# Micro.net
KiCad netlist of a schematic drawn in Altium Designer
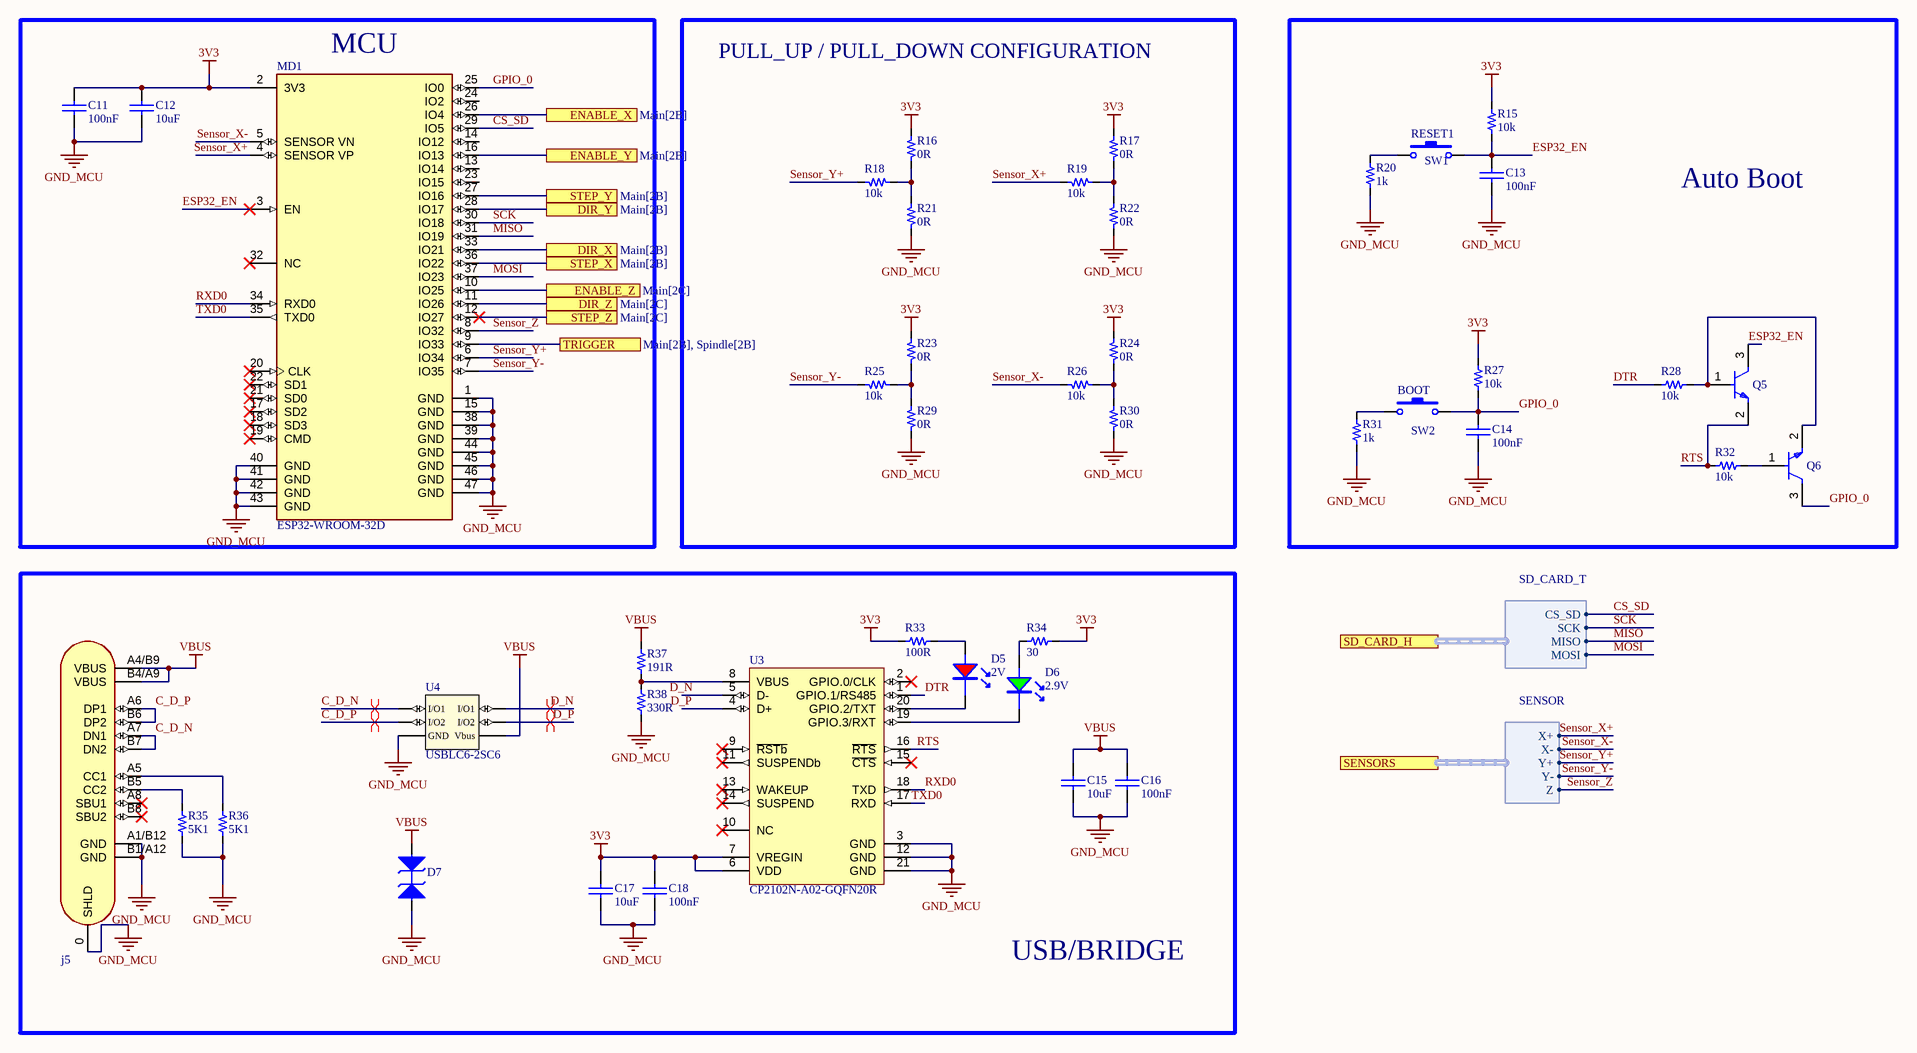
[diagram p0: Micro.SchDoc]

(export (version "E")
  (design (tool "Eeschema 10.0.6"))
  (components
    (comp (ref "C11")
      (value "100nF")
      (footprint "0603_cap")
      (description "50V 100nF X7R ±10% 0603 Ceramic Capacitors RoHS")
      (fields
        (field (name "MANUFACTURER") "FOJAN")
        (field (name "MANUFACTURER PART NUMBER") "FCC0603B104K500CT")
      )
      (libsource (lib "CNCLib") (part "Cap_100nF_0603_50V"))
    )
    (comp (ref "C12")
      (value "10uF")
      (footprint "0603_cap")
      (description "10V 10uF X5R ±10% 0603 Multilayer Ceramic Capacitors MLCC - SMD/SMT ROHS")
      (fields
        (field (name "MANUFACTURER") "CCTC")
        (field (name "MANUFACTURER PART NUMBER") "TCC0603X5R106K100CT")
      )
      (libsource (lib "CNCLib") (part "Cap_10uF_0603_10V"))
    )
    (comp (ref "C13")
      (value "100nF")
      (footprint "0603_cap")
      (description "50V 100nF X7R ±10% 0603 Ceramic Capacitors RoHS")
      (fields
        (field (name "MANUFACTURER") "FOJAN")
        (field (name "MANUFACTURER PART NUMBER") "FCC0603B104K500CT")
      )
      (libsource (lib "CNCLib") (part "Cap_100nF_0603_50V"))
    )
    (comp (ref "C14")
      (value "100nF")
      (footprint "0603_cap")
      (description "50V 100nF X7R ±10% 0603 Ceramic Capacitors RoHS")
      (fields
        (field (name "MANUFACTURER") "FOJAN")
        (field (name "MANUFACTURER PART NUMBER") "FCC0603B104K500CT")
      )
      (libsource (lib "CNCLib") (part "Cap_100nF_0603_50V"))
    )
    (comp (ref "C15")
      (value "10uF")
      (footprint "0603_cap")
      (description "10V 10uF X5R ±10% 0603 Multilayer Ceramic Capacitors MLCC - SMD/SMT ROHS")
      (fields
        (field (name "MANUFACTURER") "CCTC")
        (field (name "MANUFACTURER PART NUMBER") "TCC0603X5R106K100CT")
      )
      (libsource (lib "CNCLib") (part "Cap_10uF_0603_10V"))
    )
    (comp (ref "C16")
      (value "100nF")
      (footprint "0603_cap")
      (description "50V 100nF X7R ±10% 0603 Ceramic Capacitors RoHS")
      (fields
        (field (name "MANUFACTURER") "FOJAN")
        (field (name "MANUFACTURER PART NUMBER") "FCC0603B104K500CT")
      )
      (libsource (lib "CNCLib") (part "Cap_100nF_0603_50V"))
    )
    (comp (ref "C17")
      (value "10uF")
      (footprint "0603_cap")
      (description "10V 10uF X5R ±10% 0603 Multilayer Ceramic Capacitors MLCC - SMD/SMT ROHS")
      (fields
        (field (name "MANUFACTURER") "CCTC")
        (field (name "MANUFACTURER PART NUMBER") "TCC0603X5R106K100CT")
      )
      (libsource (lib "CNCLib") (part "Cap_10uF_0603_10V"))
    )
    (comp (ref "C18")
      (value "100nF")
      (footprint "0603_cap")
      (description "50V 100nF X7R ±10% 0603 Ceramic Capacitors RoHS")
      (fields
        (field (name "MANUFACTURER") "FOJAN")
        (field (name "MANUFACTURER PART NUMBER") "FCC0603B104K500CT")
      )
      (libsource (lib "CNCLib") (part "Cap_100nF_0603_50V"))
    )
    (comp (ref "D5")
      (value "2V")
      (footprint "0805_LED")
      (description "LED RED CLEAR 0805 SMD")
      (fields
        (field (name "MANUFACTURER") "XINGLIGHT")
        (field (name "MANUFACTURER PART NUMBER") "XL-2012SURC")
      )
      (libsource (lib "CNCLib") (part "LED_0805_RED"))
    )
    (comp (ref "D6")
      (value "2.9V")
      (footprint "0805_LED")
      (description "LED GREEN CLEAR 0805 SMD")
      (fields
        (field (name "MANUFACTURER") "XINGLIGHT")
        (field (name "MANUFACTURER PART NUMBER") "XL-2012UGC")
      )
      (libsource (lib "CNCLib") (part "LED_0805_Green"))
    )
    (comp (ref "D7")
      (value "TVS 12V")
      (footprint "SOD_123FL")
      (description "21.7A 200W@10/1000us 9.2V 7V Bidirectional 5V SOD-123FL ESD and Surge Protection (TVS/ESD) ROHS")
      (fields (field (name "MANUFACTURER") "TDSEMIC") (field (name "MANUFACTURER PART NUMBER") "SMF5.0CA"))
      (libsource (lib "CNCLib") (part "TVS_5V_1CH_BID_SOD_123FL"))
    )
    (comp (ref "j5")
      (value "USB C")
      (footprint "CON_USB_C_16P_RA")
      (description "3A USB 3.1 1 Surface Mount 16P Female -40℃~+85℃ Type-C SMD USB Connectors ROHS")
      (fields
        (field (name "MANUFACTURER") "SHOU HAN")
        (field (name "MANUFACTURER PART NUMBER") "TYPE-C-3.1-16PIN")
      )
      (libsource (lib "CNCLib") (part "CON_USB_TYPEC_16P"))
    )
    (comp (ref "MD1")
      (value "ESP32-WROOM-32D")
      (footprint "MOD_ESP32-WROOM-32_EXP")
      (description "WIFI MODULE 32MBITS SPI FLASH")
      (fields
        (field (name "MANUFACTURER") "ESPRESSIF")
        (field (name "MANUFACTURER PART NUMBER") "ESP32-WROOM-32-N4")
      )
      (libsource (lib "CNCLib") (part "CMP-194065-000003-1"))
    )
    (comp (ref "Q5")
      (value "TRANS NPN 40V 200mA SOT-23")
      (footprint "SOT_23_3")
      (description "40V 310mW 200mA NPN SOT-23 Single Bipolar Transistors RoHS")
      (fields (field (name "MANUFACTURER") "DIODES") (field (name "MANUFACTURER PART NUMBER") "MMBT3904-7-F"))
      (libsource (lib "CNCLib") (part "BJT_N_MMBT3904-7-F"))
    )
    (comp (ref "Q6")
      (value "TRANS NPN 40V 200mA SOT-23")
      (footprint "SOT_23_3")
      (description "40V 310mW 200mA NPN SOT-23 Single Bipolar Transistors RoHS")
      (fields (field (name "MANUFACTURER") "DIODES") (field (name "MANUFACTURER PART NUMBER") "MMBT3904-7-F"))
      (libsource (lib "CNCLib") (part "BJT_N_MMBT3904-7-F"))
    )
    (comp (ref "R15")
      (value "10k")
      (footprint "0603_res")
      (description "RES SMD 10k OHM 5% 1/10W 0603")
      (fields (field (name "MANUFACTURER") "FOJAN") (field (name "MANUFACTURER PART NUMBER") "FRC0603J103TS"))
      (libsource (lib "CNCLib") (part "Res_10k_0603_1/10W"))
    )
    (comp (ref "R16")
      (value "0R")
      (footprint "0603_res")
      (description "RES SMD 0R OHM 5% 1/10W 0603")
      (fields
        (field (name "MANUFACTURER") "FOJAN")
        (field (name "MANUFACTURER PART NUMBER") "FRC0603P000 TS")
      )
      (libsource (lib "CNCLib") (part "Res_0R_0603_1/10W"))
    )
    (comp (ref "R17")
      (value "0R")
      (footprint "0603_res")
      (description "RES SMD 0R OHM 5% 1/10W 0603")
      (fields
        (field (name "MANUFACTURER") "FOJAN")
        (field (name "MANUFACTURER PART NUMBER") "FRC0603P000 TS")
      )
      (libsource (lib "CNCLib") (part "Res_0R_0603_1/10W"))
    )
    (comp (ref "R18")
      (value "10k")
      (footprint "0603_res")
      (description "RES SMD 10k OHM 5% 1/10W 0603")
      (fields (field (name "MANUFACTURER") "FOJAN") (field (name "MANUFACTURER PART NUMBER") "FRC0603J103TS"))
      (libsource (lib "CNCLib") (part "Res_10k_0603_1/10W"))
    )
    (comp (ref "R19")
      (value "10k")
      (footprint "0603_res")
      (description "RES SMD 10k OHM 5% 1/10W 0603")
      (fields (field (name "MANUFACTURER") "FOJAN") (field (name "MANUFACTURER PART NUMBER") "FRC0603J103TS"))
      (libsource (lib "CNCLib") (part "Res_10k_0603_1/10W"))
    )
    (comp (ref "R20")
      (value "1k")
      (footprint "0603_res")
      (description "RES SMD 1k OHM 5% 1/10W 0603")
      (fields
        (field (name "MANUFACTURER") "FOJAN")
        (field (name "MANUFACTURER PART NUMBER") "FRC0603J102 TS")
      )
      (libsource (lib "CNCLib") (part "Res_1k_0603_1/10W"))
    )
    (comp (ref "R21")
      (value "0R")
      (footprint "0603_res")
      (description "RES SMD 0R OHM 5% 1/10W 0603")
      (fields
        (field (name "MANUFACTURER") "FOJAN")
        (field (name "MANUFACTURER PART NUMBER") "FRC0603P000 TS")
      )
      (libsource (lib "CNCLib") (part "Res_0R_0603_1/10W"))
    )
    (comp (ref "R22")
      (value "0R")
      (footprint "0603_res")
      (description "RES SMD 0R OHM 5% 1/10W 0603")
      (fields
        (field (name "MANUFACTURER") "FOJAN")
        (field (name "MANUFACTURER PART NUMBER") "FRC0603P000 TS")
      )
      (libsource (lib "CNCLib") (part "Res_0R_0603_1/10W"))
    )
    (comp (ref "R23")
      (value "0R")
      (footprint "0603_res")
      (description "RES SMD 0R OHM 5% 1/10W 0603")
      (fields
        (field (name "MANUFACTURER") "FOJAN")
        (field (name "MANUFACTURER PART NUMBER") "FRC0603P000 TS")
      )
      (libsource (lib "CNCLib") (part "Res_0R_0603_1/10W"))
    )
    (comp (ref "R24")
      (value "0R")
      (footprint "0603_res")
      (description "RES SMD 0R OHM 5% 1/10W 0603")
      (fields
        (field (name "MANUFACTURER") "FOJAN")
        (field (name "MANUFACTURER PART NUMBER") "FRC0603P000 TS")
      )
      (libsource (lib "CNCLib") (part "Res_0R_0603_1/10W"))
    )
    (comp (ref "R25")
      (value "10k")
      (footprint "0603_res")
      (description "RES SMD 10k OHM 5% 1/10W 0603")
      (fields (field (name "MANUFACTURER") "FOJAN") (field (name "MANUFACTURER PART NUMBER") "FRC0603J103TS"))
      (libsource (lib "CNCLib") (part "Res_10k_0603_1/10W"))
    )
    (comp (ref "R26")
      (value "10k")
      (footprint "0603_res")
      (description "RES SMD 10k OHM 5% 1/10W 0603")
      (fields (field (name "MANUFACTURER") "FOJAN") (field (name "MANUFACTURER PART NUMBER") "FRC0603J103TS"))
      (libsource (lib "CNCLib") (part "Res_10k_0603_1/10W"))
    )
    (comp (ref "R27")
      (value "10k")
      (footprint "0603_res")
      (description "RES SMD 10k OHM 5% 1/10W 0603")
      (fields (field (name "MANUFACTURER") "FOJAN") (field (name "MANUFACTURER PART NUMBER") "FRC0603J103TS"))
      (libsource (lib "CNCLib") (part "Res_10k_0603_1/10W"))
    )
    (comp (ref "R28")
      (value "10k")
      (footprint "0603_res")
      (description "RES SMD 10k OHM 5% 1/10W 0603")
      (fields (field (name "MANUFACTURER") "FOJAN") (field (name "MANUFACTURER PART NUMBER") "FRC0603J103TS"))
      (libsource (lib "CNCLib") (part "Res_10k_0603_1/10W"))
    )
    (comp (ref "R29")
      (value "0R")
      (footprint "0603_res")
      (description "RES SMD 0R OHM 5% 1/10W 0603")
      (fields
        (field (name "MANUFACTURER") "FOJAN")
        (field (name "MANUFACTURER PART NUMBER") "FRC0603P000 TS")
      )
      (libsource (lib "CNCLib") (part "Res_0R_0603_1/10W"))
    )
    (comp (ref "R30")
      (value "0R")
      (footprint "0603_res")
      (description "RES SMD 0R OHM 5% 1/10W 0603")
      (fields
        (field (name "MANUFACTURER") "FOJAN")
        (field (name "MANUFACTURER PART NUMBER") "FRC0603P000 TS")
      )
      (libsource (lib "CNCLib") (part "Res_0R_0603_1/10W"))
    )
    (comp (ref "R31")
      (value "1k")
      (footprint "0603_res")
      (description "RES SMD 1k OHM 5% 1/10W 0603")
      (fields
        (field (name "MANUFACTURER") "FOJAN")
        (field (name "MANUFACTURER PART NUMBER") "FRC0603J102 TS")
      )
      (libsource (lib "CNCLib") (part "Res_1k_0603_1/10W"))
    )
    (comp (ref "R32")
      (value "10k")
      (footprint "0603_res")
      (description "RES SMD 10k OHM 5% 1/10W 0603")
      (fields (field (name "MANUFACTURER") "FOJAN") (field (name "MANUFACTURER PART NUMBER") "FRC0603J103TS"))
      (libsource (lib "CNCLib") (part "Res_10k_0603_1/10W"))
    )
    (comp (ref "R33")
      (value "100R")
      (footprint "0603_res")
      (description "RES SMD 100R OHM 5% 1/10W 0603")
      (fields
        (field (name "MANUFACTURER") "FOJAN")
        (field (name "MANUFACTURER PART NUMBER") "FRC0603J101 TS")
      )
      (libsource (lib "CNCLib") (part "Res_100R_0603_1/10W"))
    )
    (comp (ref "R34")
      (value "30")
      (footprint "0603_res")
      (description "100mW 30Ω 75V ±100ppm/℃ Thick Film Resistor ±5% 0603 Chip Resistor - Surface Mount RoHS")
      (fields
        (field (name "MANUFACTURER") "FOJAN")
        (field (name "MANUFACTURER PART NUMBER") "FRC0603J300 TS")
      )
      (libsource (lib "CNCLib") (part "Res_30_0603_1/10W"))
    )
    (comp (ref "R35")
      (value "5K1")
      (footprint "0603_res")
      (description "100mW 5.1kΩ 75V ±100ppm/℃ Thick Film Resistor ±1% 0603 Chip Resistor - Surface Mount RoHS")
      (fields
        (field (name "MANUFACTURER") "FOJAN")
        (field (name "MANUFACTURER PART NUMBER") "FRC0603F5101TS")
      )
      (libsource (lib "CNCLib") (part "Res 5K1"))
    )
    (comp (ref "R36")
      (value "5K1")
      (footprint "0603_res")
      (description "100mW 5.1kΩ 75V ±100ppm/℃ Thick Film Resistor ±1% 0603 Chip Resistor - Surface Mount RoHS")
      (fields
        (field (name "MANUFACTURER") "FOJAN")
        (field (name "MANUFACTURER PART NUMBER") "FRC0603F5101TS")
      )
      (libsource (lib "CNCLib") (part "Res 5K1"))
    )
    (comp (ref "R37")
      (value "191R")
      (footprint "0603_res")
      (description "100mW Thick Film Resistor 75V ±100ppm/℃ ±1% 191Ω 0603 Chip Resistor - Surface Mount ROHS")
      (fields
        (field (name "MANUFACTURER") "FOJAN")
        (field (name "MANUFACTURER PART NUMBER") "FRC0603F1910TS")
      )
      (libsource (lib "CNCLib") (part "Res_191R_0603_1/10W"))
    )
    (comp (ref "R38")
      (value "330R")
      (footprint "0603_res")
      (description "RES SMD 330R OHM 5% 1/10W 0603")
      (fields
        (field (name "MANUFACTURER") "FOJAN")
        (field (name "MANUFACTURER PART NUMBER") "FRC0603J331 TS")
      )
      (libsource (lib "CNCLib") (part "Res_330R_0603_1/10W"))
    )
    (comp (ref "SW1")
      (value "Sw")
      (footprint "Sw_PUSH_4.5x4.5x5mm")
      (description "SWITCH TACTILE SPST-NO 0.05A 12V")
      (fields
        (field (name "MANUFACTURER") "BZCN")
        (field (name "MANUFACTURER PART NUMBER") "TSC015A05026A")
        (field (name "LAST MODIFIED BY") "N-A.Potosi")
      )
      (libsource (lib "CNCLib") (part "Sw_PUSH_4.5x4.5x5.0xmm"))
    )
    (comp (ref "SW2")
      (value "Sw")
      (footprint "Sw_PUSH_4.5x4.5x5mm")
      (description "SWITCH TACTILE SPST-NO 0.05A 12V")
      (fields
        (field (name "MANUFACTURER") "BZCN")
        (field (name "MANUFACTURER PART NUMBER") "TSC015A05026A")
        (field (name "LAST MODIFIED BY") "N-A.Potosi")
      )
      (libsource (lib "CNCLib") (part "Sw_PUSH_4.5x4.5x5.0xmm"))
    )
    (comp (ref "U3")
      (value "CP2102N-A02-GQFN20R")
      (footprint "WFQFN_20_EP_3X3MM")
      (description "IC USB TO UART BRIDGE QFN20")
      (fields (field (name "MANUFACTURER") "Silicon Labs"))
      (libsource (lib "CNCLib") (part "IC_SGL_USB2UART-BRIDGE_20QFN"))
    )
    (comp (ref "U4")
      (value "USBLC6-2SC6")
      (footprint "SOT_23_6")
      (description "TVS DIODE 5.25V 17V SOT23-6")
      (fields (field (name "MANUFACTURER") "STMicroelectronics"))
      (libsource (lib "CNCLib") (part "TVS_5.25V_2CH_SOT_23_6"))
    )
  )
  (nets
    (net (code "3") (name "/CS_SD") (class "Default")
      (node (ref "MD1") (pin "29") (pinfunction "IO5_29") (pintype "bidirectional"))
    )
    (net (code "4") (name "/C_D_N") (class "Default")
      (node (ref "U4") (pin "1") (pinfunction "I/O1_1") (pintype "bidirectional"))
      (node (ref "j5") (pin "A7") (pinfunction "DN1_A7") (pintype "bidirectional"))
      (node (ref "j5") (pin "B7") (pinfunction "DN2_B7") (pintype "bidirectional"))
    )
    (net (code "5") (name "/C_D_P") (class "Default")
      (node (ref "U4") (pin "3") (pinfunction "I/O2_3") (pintype "bidirectional"))
      (node (ref "j5") (pin "A6") (pinfunction "DP1_A6") (pintype "bidirectional"))
      (node (ref "j5") (pin "B6") (pinfunction "DP2_B6") (pintype "bidirectional"))
    )
    (net (code "6") (name "/DIR_X") (class "Default")
      (node (ref "MD1") (pin "33") (pinfunction "IO21_33") (pintype "bidirectional"))
    )
    (net (code "7") (name "/DIR_Y") (class "Default")
      (node (ref "MD1") (pin "28") (pinfunction "IO17_28") (pintype "bidirectional"))
    )
    (net (code "8") (name "/DIR_Z") (class "Default")
      (node (ref "MD1") (pin "11") (pinfunction "IO26_11") (pintype "bidirectional"))
    )
    (net (code "9") (name "/DTR") (class "Default")
      (node (ref "R28") (pin "2") (pinfunction "2_2") (pintype "passive"))
      (node (ref "U3") (pin "1") (pinfunction "GPIO.1/RS485_1") (pintype "bidirectional"))
    )
    (net (code "10") (name "/D_N") (class "Default")
      (node (ref "U3") (pin "5") (pinfunction "D-_5") (pintype "bidirectional"))
      (node (ref "U4") (pin "6") (pinfunction "I/O1_6") (pintype "bidirectional"))
    )
    (net (code "11") (name "/D_P") (class "Default")
      (node (ref "U3") (pin "4") (pinfunction "D+_4") (pintype "bidirectional"))
      (node (ref "U4") (pin "4") (pinfunction "I/O2_4") (pintype "bidirectional"))
    )
    (net (code "12") (name "/ENABLE_X") (class "Default")
      (node (ref "MD1") (pin "26") (pinfunction "IO4_26") (pintype "bidirectional"))
    )
    (net (code "13") (name "/ENABLE_Y") (class "Default")
      (node (ref "MD1") (pin "16") (pinfunction "IO13_16") (pintype "bidirectional"))
    )
    (net (code "14") (name "/ENABLE_Z") (class "Default")
      (node (ref "MD1") (pin "10") (pinfunction "IO25_10") (pintype "bidirectional"))
    )
    (net (code "15") (name "/ESP32_EN") (class "Default")
      (node (ref "C13") (pin "1") (pinfunction "1_1") (pintype "passive"))
      (node (ref "MD1") (pin "3") (pinfunction "EN_3") (pintype "input"))
      (node (ref "Q5") (pin "3") (pinfunction "C_3") (pintype "passive"))
      (node (ref "R15") (pin "1") (pinfunction "1_1") (pintype "passive"))
      (node (ref "SW1") (pin "2") (pinfunction "2_2") (pintype "passive"))
    )
    (net (code "16") (name "/GPIO_0") (class "Default")
      (node (ref "C14") (pin "1") (pinfunction "1_1") (pintype "passive"))
      (node (ref "MD1") (pin "25") (pinfunction "IO0_25") (pintype "bidirectional"))
      (node (ref "Q6") (pin "3") (pinfunction "C_3") (pintype "passive"))
      (node (ref "R27") (pin "1") (pinfunction "1_1") (pintype "passive"))
      (node (ref "SW2") (pin "2") (pinfunction "2_2") (pintype "passive"))
    )
    (net (code "17") (name "/MISO") (class "Default")
      (node (ref "MD1") (pin "31") (pinfunction "IO19_31") (pintype "bidirectional"))
    )
    (net (code "18") (name "/MOSI") (class "Default")
      (node (ref "MD1") (pin "37") (pinfunction "IO23_37") (pintype "bidirectional"))
    )
    (net (code "19") (name "/RTS") (class "Default")
      (node (ref "Q5") (pin "2") (pinfunction "E_2") (pintype "passive"))
      (node (ref "R32") (pin "2") (pinfunction "2_2") (pintype "passive"))
      (node (ref "U3") (pin "16") (pinfunction "~{RTS}_16") (pintype "output"))
    )
    (net (code "20") (name "/RXD0") (class "Default")
      (node (ref "MD1") (pin "34") (pinfunction "RXD0_34") (pintype "input"))
      (node (ref "U3") (pin "18") (pinfunction "TXD_18") (pintype "output"))
    )
    (net (code "21") (name "/SCK") (class "Default")
      (node (ref "MD1") (pin "30") (pinfunction "IO18_30") (pintype "bidirectional"))
    )
    (net (code "22") (name "/STEP_X") (class "Default")
      (node (ref "MD1") (pin "36") (pinfunction "IO22_36") (pintype "bidirectional"))
    )
    (net (code "23") (name "/STEP_Y") (class "Default")
      (node (ref "MD1") (pin "27") (pinfunction "IO16_27") (pintype "bidirectional"))
    )
    (net (code "24") (name "/STEP_Z") (class "Default")
      (node (ref "MD1") (pin "12") (pinfunction "IO27_12") (pintype "bidirectional+no_connect"))
    )
    (net (code "25") (name "/Sensor_X+") (class "Default")
      (node (ref "MD1") (pin "4") (pinfunction "SENSOR_VP_4") (pintype "bidirectional"))
      (node (ref "R19") (pin "2") (pinfunction "2_2") (pintype "passive"))
    )
    (net (code "26") (name "/Sensor_X-") (class "Default")
      (node (ref "MD1") (pin "5") (pinfunction "SENSOR_VN_5") (pintype "bidirectional"))
      (node (ref "R26") (pin "2") (pinfunction "2_2") (pintype "passive"))
    )
    (net (code "27") (name "/Sensor_Y+") (class "Default")
      (node (ref "MD1") (pin "6") (pinfunction "IO34_6") (pintype "bidirectional"))
      (node (ref "R18") (pin "2") (pinfunction "2_2") (pintype "passive"))
    )
    (net (code "28") (name "/Sensor_Y-") (class "Default")
      (node (ref "MD1") (pin "7") (pinfunction "IO35_7") (pintype "bidirectional"))
      (node (ref "R25") (pin "2") (pinfunction "2_2") (pintype "passive"))
    )
    (net (code "29") (name "/Sensor_Z") (class "Default")
      (node (ref "MD1") (pin "8") (pinfunction "IO32_8") (pintype "bidirectional"))
    )
    (net (code "30") (name "/TRIGGER") (class "Default")
      (node (ref "MD1") (pin "9") (pinfunction "IO33_9") (pintype "bidirectional"))
    )
    (net (code "31") (name "/TXD0") (class "Default")
      (node (ref "MD1") (pin "35") (pinfunction "TXD0_35") (pintype "output"))
      (node (ref "U3") (pin "17") (pinfunction "RXD_17") (pintype "input"))
    )
    (net (code "34") (name "3V3") (class "Default")
      (node (ref "C11") (pin "1") (pinfunction "1_1") (pintype "passive"))
      (node (ref "C12") (pin "1") (pinfunction "1_1") (pintype "passive"))
      (node (ref "C17") (pin "1") (pinfunction "1_1") (pintype "passive"))
      (node (ref "C18") (pin "1") (pinfunction "1_1") (pintype "passive"))
      (node (ref "MD1") (pin "2") (pinfunction "3V3_2") (pintype "power_in"))
      (node (ref "R15") (pin "2") (pinfunction "2_2") (pintype "passive"))
      (node (ref "R16") (pin "1") (pinfunction "1_1") (pintype "passive"))
      (node (ref "R17") (pin "1") (pinfunction "1_1") (pintype "passive"))
      (node (ref "R23") (pin "1") (pinfunction "1_1") (pintype "passive"))
      (node (ref "R24") (pin "1") (pinfunction "1_1") (pintype "passive"))
      (node (ref "R27") (pin "2") (pinfunction "2_2") (pintype "passive"))
      (node (ref "R33") (pin "1") (pinfunction "1_1") (pintype "passive"))
      (node (ref "R34") (pin "2") (pinfunction "2_2") (pintype "passive"))
      (node (ref "U3") (pin "6") (pinfunction "VDD_6") (pintype "power_in"))
      (node (ref "U3") (pin "7") (pinfunction "VREGIN_7") (pintype "power_in"))
    )
    (net (code "35") (name "GND_MCU") (class "Default")
      (node (ref "C11") (pin "2") (pinfunction "2_2") (pintype "passive"))
      (node (ref "C12") (pin "2") (pinfunction "2_2") (pintype "passive"))
      (node (ref "C13") (pin "2") (pinfunction "2_2") (pintype "passive"))
      (node (ref "C14") (pin "2") (pinfunction "2_2") (pintype "passive"))
      (node (ref "C15") (pin "2") (pinfunction "2_2") (pintype "passive"))
      (node (ref "C16") (pin "2") (pinfunction "2_2") (pintype "passive"))
      (node (ref "C17") (pin "2") (pinfunction "2_2") (pintype "passive"))
      (node (ref "C18") (pin "2") (pinfunction "2_2") (pintype "passive"))
      (node (ref "D7") (pin "2") (pinfunction "2_2") (pintype "passive"))
      (node (ref "MD1") (pin "1") (pinfunction "GND_1") (pintype "power_in"))
      (node (ref "MD1") (pin "15") (pinfunction "GND_15") (pintype "power_in"))
      (node (ref "MD1") (pin "38") (pinfunction "GND_38") (pintype "power_in"))
      (node (ref "MD1") (pin "39") (pinfunction "GND_39") (pintype "power_in"))
      (node (ref "MD1") (pin "40") (pinfunction "GND_40") (pintype "passive"))
      (node (ref "MD1") (pin "41") (pinfunction "GND_41") (pintype "passive"))
      (node (ref "MD1") (pin "42") (pinfunction "GND_42") (pintype "passive"))
      (node (ref "MD1") (pin "43") (pinfunction "GND_43") (pintype "passive"))
      (node (ref "MD1") (pin "44") (pinfunction "GND_44") (pintype "passive"))
      (node (ref "MD1") (pin "45") (pinfunction "GND_45") (pintype "passive"))
      (node (ref "MD1") (pin "46") (pinfunction "GND_46") (pintype "passive"))
      (node (ref "MD1") (pin "47") (pinfunction "GND_47") (pintype "passive"))
      (node (ref "R20") (pin "1") (pinfunction "1_1") (pintype "passive"))
      (node (ref "R21") (pin "1") (pinfunction "1_1") (pintype "passive"))
      (node (ref "R22") (pin "1") (pinfunction "1_1") (pintype "passive"))
      (node (ref "R29") (pin "1") (pinfunction "1_1") (pintype "passive"))
      (node (ref "R30") (pin "1") (pinfunction "1_1") (pintype "passive"))
      (node (ref "R31") (pin "1") (pinfunction "1_1") (pintype "passive"))
      (node (ref "R35") (pin "1") (pinfunction "1_1") (pintype "passive"))
      (node (ref "R36") (pin "1") (pinfunction "1_1") (pintype "passive"))
      (node (ref "R38") (pin "1") (pinfunction "1_1") (pintype "passive"))
      (node (ref "U3") (pin "12") (pinfunction "GND_12") (pintype "power_in"))
      (node (ref "U3") (pin "21") (pinfunction "GND_21") (pintype "power_in"))
      (node (ref "U3") (pin "3") (pinfunction "GND_3") (pintype "power_in"))
      (node (ref "U4") (pin "2") (pinfunction "GND_2") (pintype "power_in"))
      (node (ref "j5") (pin "0") (pinfunction "SHLD_0") (pintype "passive"))
      (node (ref "j5") (pin "A1/B12") (pinfunction "GND_A1/B12") (pintype "power_in"))
      (node (ref "j5") (pin "B1/A12") (pinfunction "GND_B1/A12") (pintype "power_in"))
    )
    (net (code "36") (name "Net-(D5-A)") (class "Default")
      (node (ref "D5") (pin "1") (pinfunction "A_1") (pintype "passive"))
      (node (ref "R33") (pin "2") (pinfunction "2_2") (pintype "passive"))
    )
    (net (code "37") (name "Net-(D6-A)") (class "Default")
      (node (ref "D6") (pin "1") (pinfunction "A_1") (pintype "passive"))
      (node (ref "R34") (pin "1") (pinfunction "1_1") (pintype "passive"))
    )
    (net (code "38") (name "Net-(Q5-B)") (class "Default")
      (node (ref "Q5") (pin "1") (pinfunction "B_1") (pintype "passive"))
      (node (ref "Q6") (pin "2") (pinfunction "E_2") (pintype "passive"))
      (node (ref "R28") (pin "1") (pinfunction "1_1") (pintype "passive"))
    )
    (net (code "39") (name "Net-(Q6-B)") (class "Default")
      (node (ref "Q6") (pin "1") (pinfunction "B_1") (pintype "passive"))
      (node (ref "R32") (pin "1") (pinfunction "1_1") (pintype "passive"))
    )
    (net (code "40") (name "Net-(R16-Pad2)") (class "Default")
      (node (ref "R16") (pin "2") (pinfunction "2_2") (pintype "passive"))
      (node (ref "R18") (pin "1") (pinfunction "1_1") (pintype "passive"))
      (node (ref "R21") (pin "2") (pinfunction "2_2") (pintype "passive"))
    )
    (net (code "41") (name "Net-(R17-Pad2)") (class "Default")
      (node (ref "R17") (pin "2") (pinfunction "2_2") (pintype "passive"))
      (node (ref "R19") (pin "1") (pinfunction "1_1") (pintype "passive"))
      (node (ref "R22") (pin "2") (pinfunction "2_2") (pintype "passive"))
    )
    (net (code "42") (name "Net-(R20-Pad2)") (class "Default")
      (node (ref "R20") (pin "2") (pinfunction "2_2") (pintype "passive"))
      (node (ref "SW1") (pin "1") (pinfunction "1_1") (pintype "passive"))
    )
    (net (code "43") (name "Net-(R23-Pad2)") (class "Default")
      (node (ref "R23") (pin "2") (pinfunction "2_2") (pintype "passive"))
      (node (ref "R25") (pin "1") (pinfunction "1_1") (pintype "passive"))
      (node (ref "R29") (pin "2") (pinfunction "2_2") (pintype "passive"))
    )
    (net (code "44") (name "Net-(R24-Pad2)") (class "Default")
      (node (ref "R24") (pin "2") (pinfunction "2_2") (pintype "passive"))
      (node (ref "R26") (pin "1") (pinfunction "1_1") (pintype "passive"))
      (node (ref "R30") (pin "2") (pinfunction "2_2") (pintype "passive"))
    )
    (net (code "45") (name "Net-(R31-Pad2)") (class "Default")
      (node (ref "R31") (pin "2") (pinfunction "2_2") (pintype "passive"))
      (node (ref "SW2") (pin "1") (pinfunction "1_1") (pintype "passive"))
    )
    (net (code "46") (name "Net-(U3-GPIO.2{slash}TXT)") (class "Default")
      (node (ref "D5") (pin "2") (pinfunction "2_2") (pintype "passive"))
      (node (ref "U3") (pin "20") (pinfunction "GPIO.2/TXT_20") (pintype "bidirectional"))
    )
    (net (code "47") (name "Net-(U3-GPIO.3{slash}RXT)") (class "Default")
      (node (ref "D6") (pin "2") (pinfunction "2_2") (pintype "passive"))
      (node (ref "U3") (pin "19") (pinfunction "GPIO.3/RXT_19") (pintype "bidirectional"))
    )
    (net (code "48") (name "Net-(U3-VBUS)") (class "Default")
      (node (ref "R37") (pin "1") (pinfunction "1_1") (pintype "passive"))
      (node (ref "R38") (pin "2") (pinfunction "2_2") (pintype "passive"))
      (node (ref "U3") (pin "8") (pinfunction "VBUS_8") (pintype "power_in"))
    )
    (net (code "49") (name "Net-(j5-CC1)") (class "Default")
      (node (ref "R36") (pin "2") (pinfunction "2_2") (pintype "passive"))
      (node (ref "j5") (pin "A5") (pinfunction "CC1_A5") (pintype "bidirectional"))
    )
    (net (code "50") (name "Net-(j5-CC2)") (class "Default")
      (node (ref "R35") (pin "2") (pinfunction "2_2") (pintype "passive"))
      (node (ref "j5") (pin "B5") (pinfunction "CC2_B5") (pintype "bidirectional"))
    )
    (net (code "51") (name "VBUS") (class "Default")
      (node (ref "C15") (pin "1") (pinfunction "1_1") (pintype "passive"))
      (node (ref "C16") (pin "1") (pinfunction "1_1") (pintype "passive"))
      (node (ref "D7") (pin "1") (pinfunction "1_1") (pintype "passive"))
      (node (ref "R37") (pin "2") (pinfunction "2_2") (pintype "passive"))
      (node (ref "U4") (pin "5") (pinfunction "Vbus_5") (pintype "power_in"))
      (node (ref "j5") (pin "A4/B9") (pinfunction "VBUS_A4/B9") (pintype "power_in"))
      (node (ref "j5") (pin "B4/A9") (pinfunction "VBUS_B4/A9") (pintype "power_in"))
    )
    (net (code "52") (name "unconnected-(MD1-CLK-Pad20)") (class "Default")
      (node (ref "MD1") (pin "20") (pinfunction "CLK_20") (pintype "input+no_connect"))
    )
    (net (code "53") (name "unconnected-(MD1-CMD-Pad19)") (class "Default")
      (node (ref "MD1") (pin "19") (pinfunction "CMD_19") (pintype "bidirectional+no_connect"))
    )
    (net (code "54") (name "unconnected-(MD1-IO2-Pad24)") (class "Default")
      (node (ref "MD1") (pin "24") (pinfunction "IO2_24") (pintype "bidirectional"))
    )
    (net (code "55") (name "unconnected-(MD1-IO12-Pad14)") (class "Default")
      (node (ref "MD1") (pin "14") (pinfunction "IO12_14") (pintype "bidirectional"))
    )
    (net (code "56") (name "unconnected-(MD1-IO14-Pad13)") (class "Default")
      (node (ref "MD1") (pin "13") (pinfunction "IO14_13") (pintype "bidirectional"))
    )
    (net (code "57") (name "unconnected-(MD1-IO15-Pad23)") (class "Default")
      (node (ref "MD1") (pin "23") (pinfunction "IO15_23") (pintype "bidirectional"))
    )
    (net (code "58") (name "unconnected-(MD1-NC-Pad32)") (class "Default")
      (node (ref "MD1") (pin "32") (pinfunction "NC_32") (pintype "passive+no_connect"))
    )
    (net (code "59") (name "unconnected-(MD1-SD0-Pad21)") (class "Default")
      (node (ref "MD1") (pin "21") (pinfunction "SD0_21") (pintype "bidirectional+no_connect"))
    )
    (net (code "60") (name "unconnected-(MD1-SD1-Pad22)") (class "Default")
      (node (ref "MD1") (pin "22") (pinfunction "SD1_22") (pintype "bidirectional+no_connect"))
    )
    (net (code "61") (name "unconnected-(MD1-SD2-Pad17)") (class "Default")
      (node (ref "MD1") (pin "17") (pinfunction "SD2_17") (pintype "bidirectional+no_connect"))
    )
    (net (code "62") (name "unconnected-(MD1-SD3-Pad18)") (class "Default")
      (node (ref "MD1") (pin "18") (pinfunction "SD3_18") (pintype "bidirectional+no_connect"))
    )
    (net (code "63") (name "unconnected-(U3-GPIO.0{slash}CLK-Pad2)") (class "Default")
      (node (ref "U3") (pin "2") (pinfunction "GPIO.0/CLK_2") (pintype "bidirectional+no_connect"))
    )
    (net (code "64") (name "unconnected-(U3-NC-Pad10)") (class "Default")
      (node (ref "U3") (pin "10") (pinfunction "NC_10") (pintype "passive+no_connect"))
    )
    (net (code "65") (name "unconnected-(U3-SUSPEND-Pad14)") (class "Default")
      (node (ref "U3") (pin "14") (pinfunction "SUSPEND_14") (pintype "output+no_connect"))
    )
    (net (code "66") (name "unconnected-(U3-SUSPENDb-Pad11)") (class "Default")
      (node (ref "U3") (pin "11") (pinfunction "SUSPENDb_11") (pintype "output+no_connect"))
    )
    (net (code "67") (name "unconnected-(U3-WAKEUP-Pad13)") (class "Default")
      (node (ref "U3") (pin "13") (pinfunction "WAKEUP_13") (pintype "input+no_connect"))
    )
    (net (code "68") (name "unconnected-(U3-~{CTS}-Pad15)") (class "Default")
      (node (ref "U3") (pin "15") (pinfunction "~{CTS}_15") (pintype "input+no_connect"))
    )
    (net (code "69") (name "unconnected-(U3-~{RSTb}-Pad9)") (class "Default")
      (node (ref "U3") (pin "9") (pinfunction "~{RSTb}_9") (pintype "input+no_connect"))
    )
    (net (code "70") (name "unconnected-(j5-SBU1-PadA8)") (class "Default")
      (node (ref "j5") (pin "A8") (pinfunction "SBU1_A8") (pintype "bidirectional+no_connect"))
    )
    (net (code "71") (name "unconnected-(j5-SBU2-PadB8)") (class "Default")
      (node (ref "j5") (pin "B8") (pinfunction "SBU2_B8") (pintype "bidirectional+no_connect"))
    )
  )
)
